# io-devices.net
KiCad netlist of a schematic drawn in Altium Designer
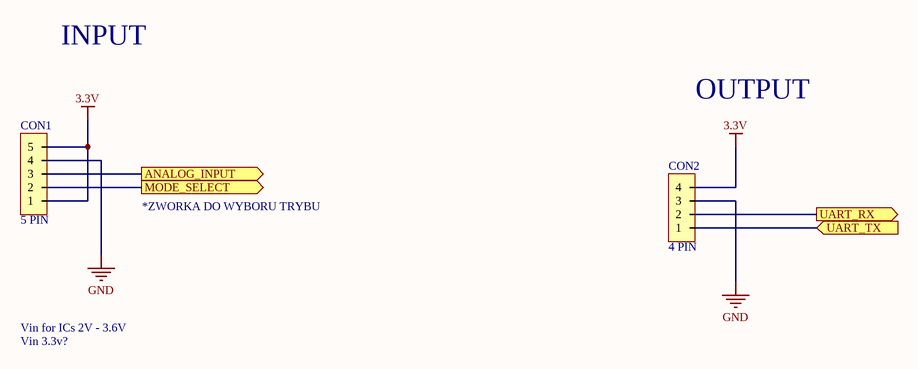
[diagram p0: io-devices.SchDoc]

(export (version "E")
  (design (tool "Eeschema 10.0.6"))
  (components
    (comp (ref "CON1")
      (value "5 PIN")
      (footprint "Goldpin 2.54mm 5P")
      (libsource (lib "sigma-delta-adc-uart") (part "5 PIN"))
    )
    (comp (ref "CON2")
      (value "4 PIN")
      (footprint "Goldpin 2.54MM 4P")
      (libsource (lib "sigma-delta-adc-uart") (part "4 PIN"))
    )
  )
  (nets
    (net (code "1") (name "/ANALOG_INPUT") (class "Default")
      (node (ref "CON1") (pin "3") (pinfunction "3_3") (pintype "passive"))
    )
    (net (code "2") (name "/MODE_SELECT") (class "Default")
      (node (ref "CON1") (pin "2") (pinfunction "2_2") (pintype "passive"))
    )
    (net (code "3") (name "/UART_RX") (class "Default")
      (node (ref "CON2") (pin "2") (pinfunction "2_2") (pintype "passive"))
    )
    (net (code "4") (name "/UART_TX") (class "Default")
      (node (ref "CON2") (pin "1") (pinfunction "1_1") (pintype "passive"))
    )
    (net (code "5") (name "3.3V") (class "Default")
      (node (ref "CON1") (pin "1") (pinfunction "1_1") (pintype "passive"))
      (node (ref "CON1") (pin "5") (pinfunction "5_5") (pintype "passive"))
      (node (ref "CON2") (pin "4") (pinfunction "4_4") (pintype "passive"))
    )
    (net (code "6") (name "GND") (class "Default")
      (node (ref "CON1") (pin "4") (pinfunction "4_4") (pintype "passive"))
      (node (ref "CON2") (pin "3") (pinfunction "3_3") (pintype "passive"))
    )
  )
)
